# INA260-Evaluation.net
KiCad netlist of a schematic drawn in EAGLE
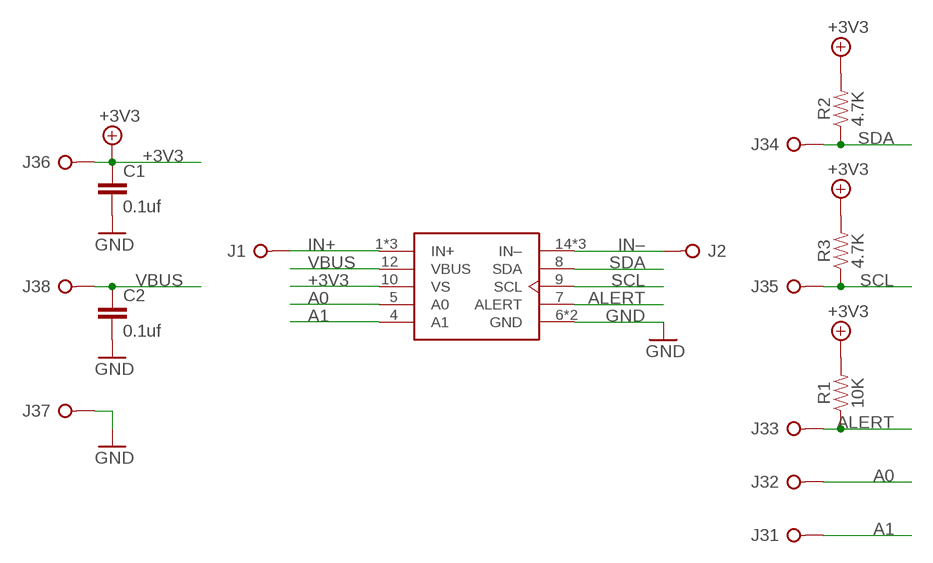
[diagram p0: schematic, sheet 1]

(export (version "E")
  (design (tool "Eeschema 10.0.6"))
  (components
    (comp (ref "C1")
      (value "0.1uf")
      (footprint "eagle-import:CAPACITOR-0805")
      (libsource (lib "eagle-import") (part "CAPACITOR-0805"))
    )
    (comp (ref "C2")
      (value "0.1uf")
      (footprint "eagle-import:CAPACITOR-0805")
      (libsource (lib "eagle-import") (part "CAPACITOR-0805"))
    )
    (comp (ref "IC1")
      (value "INA260")
      (footprint "eagle-import:TSSOP-16")
      (libsource (lib "eagle-import") (part "INA260"))
    )
    (comp (ref "J1")
      (value "PINHD-1X1BIG")
      (footprint "eagle-import:1X01-BIG")
      (libsource (lib "eagle-import") (part "PINHD-1X1BIG"))
    )
    (comp (ref "J2")
      (value "PINHD-1X1BIG")
      (footprint "eagle-import:1X01-BIG")
      (libsource (lib "eagle-import") (part "PINHD-1X1BIG"))
    )
    (comp (ref "J3")
      (value "PINHD-1X8")
      (footprint "eagle-import:1X08")
      (libsource (lib "eagle-import") (part "PINHD-1X8"))
    )
    (comp (ref "R1")
      (value "10K")
      (footprint "eagle-import:RESISTOR-0805")
      (libsource (lib "eagle-import") (part "RESISTOR-0805"))
    )
    (comp (ref "R2")
      (value "4.7K")
      (footprint "eagle-import:RESISTOR-0805")
      (libsource (lib "eagle-import") (part "RESISTOR-0805"))
    )
    (comp (ref "R3")
      (value "4.7K")
      (footprint "eagle-import:RESISTOR-0805")
      (libsource (lib "eagle-import") (part "RESISTOR-0805"))
    )
  )
  (nets
    (net (code "1") (name "+3V3") (class "Default")
      (node (ref "C1") (pin "1") (pinfunction "1_1") (pintype "passive"))
      (node (ref "IC1") (pin "10") (pinfunction "VS_10") (pintype "power_in"))
      (node (ref "J3") (pin "6") (pinfunction "KL_6") (pintype "passive"))
      (node (ref "R1") (pin "2") (pinfunction "2_2") (pintype "passive"))
      (node (ref "R2") (pin "2") (pinfunction "2_2") (pintype "passive"))
      (node (ref "R3") (pin "2") (pinfunction "2_2") (pintype "passive"))
    )
    (net (code "2") (name "/A0") (class "Default")
      (node (ref "IC1") (pin "5") (pinfunction "A0_5") (pintype "input"))
      (node (ref "J3") (pin "2") (pinfunction "KL_2") (pintype "passive"))
    )
    (net (code "3") (name "/A1") (class "Default")
      (node (ref "IC1") (pin "4") (pinfunction "A1_4") (pintype "input"))
      (node (ref "J3") (pin "1") (pinfunction "KL_1") (pintype "passive"))
    )
    (net (code "4") (name "/ALERT") (class "Default")
      (node (ref "IC1") (pin "7") (pinfunction "ALERT_7") (pintype "open_collector"))
      (node (ref "J3") (pin "3") (pinfunction "KL_3") (pintype "passive"))
      (node (ref "R1") (pin "1") (pinfunction "1_1") (pintype "passive"))
    )
    (net (code "5") (name "/IN+") (class "Default")
      (node (ref "IC1") (pin "1") (pinfunction "IN+_1") (pintype "passive"))
      (node (ref "IC1") (pin "2") (pinfunction "IN+_2") (pintype "passive"))
      (node (ref "IC1") (pin "3") (pinfunction "IN+_3") (pintype "passive"))
      (node (ref "J1") (pin "1") (pinfunction "KL_1") (pintype "passive"))
    )
    (net (code "6") (name "/IN–") (class "Default")
      (node (ref "IC1") (pin "14") (pinfunction "IN–_14") (pintype "passive"))
      (node (ref "IC1") (pin "15") (pinfunction "IN–_15") (pintype "passive"))
      (node (ref "IC1") (pin "16") (pinfunction "IN–_16") (pintype "passive"))
      (node (ref "J2") (pin "1") (pinfunction "KL_1") (pintype "passive"))
    )
    (net (code "7") (name "/SCL") (class "Default")
      (node (ref "IC1") (pin "9") (pinfunction "SCL_9") (pintype "open_collector"))
      (node (ref "J3") (pin "5") (pinfunction "KL_5") (pintype "passive"))
      (node (ref "R3") (pin "1") (pinfunction "1_1") (pintype "passive"))
    )
    (net (code "8") (name "/SDA") (class "Default")
      (node (ref "IC1") (pin "8") (pinfunction "SDA_8") (pintype "open_collector"))
      (node (ref "J3") (pin "4") (pinfunction "KL_4") (pintype "passive"))
      (node (ref "R2") (pin "1") (pinfunction "1_1") (pintype "passive"))
    )
    (net (code "9") (name "/VBUS") (class "Default")
      (node (ref "C2") (pin "1") (pinfunction "1_1") (pintype "passive"))
      (node (ref "IC1") (pin "12") (pinfunction "VBUS_12") (pintype "input"))
      (node (ref "J3") (pin "8") (pinfunction "KL_8") (pintype "passive"))
    )
    (net (code "10") (name "GND") (class "Default")
      (node (ref "C1") (pin "2") (pinfunction "2_2") (pintype "passive"))
      (node (ref "C2") (pin "2") (pinfunction "2_2") (pintype "passive"))
      (node (ref "IC1") (pin "11") (pinfunction "GND_11") (pintype "power_in"))
      (node (ref "IC1") (pin "6") (pinfunction "GND_6") (pintype "power_in"))
      (node (ref "J3") (pin "7") (pinfunction "KL_7") (pintype "passive"))
    )
  )
)
